# SCH-EC_port.net
KiCad netlist of a schematic drawn in Altium Designer
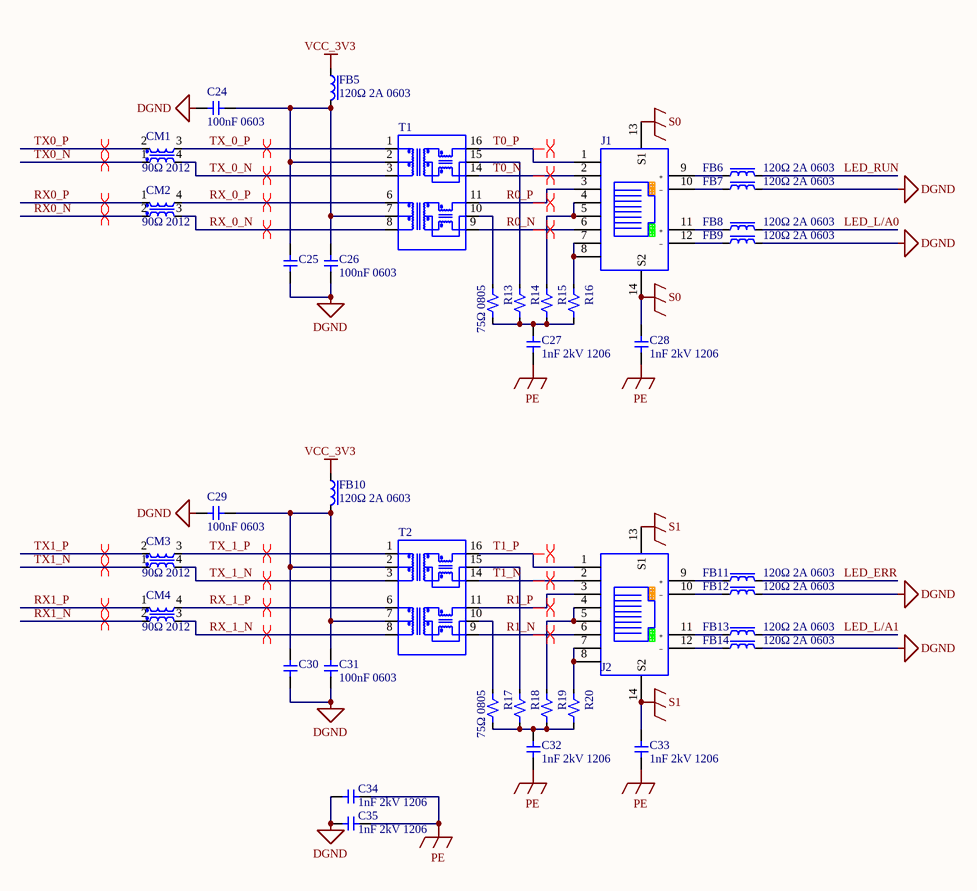
[diagram p0: SCH-EC_port.SchDoc]

(export (version "E")
  (design (tool "Eeschema 10.0.6"))
  (components
    (comp (ref "C24")
      (value "100nF 0603")
      (footprint "CAPC1608X08 (0603)")
      (description "贴片MLCC电容 100nF 50V X7R 10% 0603")
      (fields
        (field (name "1ST PARTNUMBER") "CC0603KRX7R9BB104")
        (field (name "2ND PARTNUMBER") "CGA3E2X7R1H104K080AA")
      )
      (libsource (lib "12-无源器件") (part "100nF 0603"))
    )
    (comp (ref "C25")
      (value "100nF 0603")
      (footprint "CAPC1608X08 (0603)")
      (description "贴片MLCC电容 100nF 50V X7R 10% 0603")
      (fields
        (field (name "1ST PARTNUMBER") "CC0603KRX7R9BB104")
        (field (name "2ND PARTNUMBER") "CGA3E2X7R1H104K080AA")
      )
      (libsource (lib "12-无源器件") (part "100nF 0603"))
    )
    (comp (ref "C26")
      (value "100nF 0603")
      (footprint "CAPC1608X08 (0603)")
      (description "贴片MLCC电容 100nF 50V X7R 10% 0603")
      (fields
        (field (name "1ST PARTNUMBER") "CC0603KRX7R9BB104")
        (field (name "2ND PARTNUMBER") "CGA3E2X7R1H104K080AA")
      )
      (libsource (lib "12-无源器件") (part "100nF 0603"))
    )
    (comp (ref "C27")
      (value "1nF 2kV 1206")
      (footprint "CAPC3216X16 (1206)")
      (description "贴片MLCC电容 1.0nF 2KV X7R 10% 1206")
      (fields (field (name "1ST PARTNUMBER") "CC1206KKX7RDBB102"))
      (libsource (lib "") (part "1nF 2kV 1206_1"))
    )
    (comp (ref "C28")
      (value "1nF 2kV 1206")
      (footprint "CAPC3216X16 (1206)")
      (description "贴片MLCC电容 1.0nF 2KV X7R 10% 1206")
      (fields (field (name "1ST PARTNUMBER") "CC1206KKX7RDBB102"))
      (libsource (lib "12-无源器件") (part "1nF 2kV 1206"))
    )
    (comp (ref "C29")
      (value "100nF 0603")
      (footprint "CAPC1608X08 (0603)")
      (description "贴片MLCC电容 100nF 50V X7R 10% 0603")
      (fields
        (field (name "1ST PARTNUMBER") "CC0603KRX7R9BB104")
        (field (name "2ND PARTNUMBER") "CGA3E2X7R1H104K080AA")
      )
      (libsource (lib "12-无源器件") (part "100nF 0603"))
    )
    (comp (ref "C30")
      (value "100nF 0603")
      (footprint "CAPC1608X08 (0603)")
      (description "贴片MLCC电容 100nF 50V X7R 10% 0603")
      (fields
        (field (name "1ST PARTNUMBER") "CC0603KRX7R9BB104")
        (field (name "2ND PARTNUMBER") "CGA3E2X7R1H104K080AA")
      )
      (libsource (lib "12-无源器件") (part "100nF 0603"))
    )
    (comp (ref "C31")
      (value "100nF 0603")
      (footprint "CAPC1608X08 (0603)")
      (description "贴片MLCC电容 100nF 50V X7R 10% 0603")
      (fields
        (field (name "1ST PARTNUMBER") "CC0603KRX7R9BB104")
        (field (name "2ND PARTNUMBER") "CGA3E2X7R1H104K080AA")
      )
      (libsource (lib "12-无源器件") (part "100nF 0603"))
    )
    (comp (ref "C32")
      (value "1nF 2kV 1206")
      (footprint "CAPC3216X16 (1206)")
      (description "贴片MLCC电容 1.0nF 2KV X7R 10% 1206")
      (fields (field (name "1ST PARTNUMBER") "CC1206KKX7RDBB102"))
      (libsource (lib "") (part "1nF 2kV 1206_1"))
    )
    (comp (ref "C33")
      (value "1nF 2kV 1206")
      (footprint "CAPC3216X16 (1206)")
      (description "贴片MLCC电容 1.0nF 2KV X7R 10% 1206")
      (fields (field (name "1ST PARTNUMBER") "CC1206KKX7RDBB102"))
      (libsource (lib "12-无源器件") (part "1nF 2kV 1206"))
    )
    (comp (ref "C34")
      (value "1nF 2kV 1206")
      (footprint "CAPC3216X16 (1206)")
      (description "贴片MLCC电容 1.0nF 2KV X7R 10% 1206")
      (fields (field (name "1ST PARTNUMBER") "CC1206KKX7RDBB102"))
      (libsource (lib "") (part "1nF 2kV 1206_1"))
    )
    (comp (ref "C35")
      (value "1nF 2kV 1206")
      (footprint "CAPC3216X16 (1206)")
      (description "贴片MLCC电容 1.0nF 2KV X7R 10% 1206")
      (fields (field (name "1ST PARTNUMBER") "CC1206KKX7RDBB102"))
      (libsource (lib "") (part "1nF 2kV 1206_1"))
    )
    (comp (ref "CM1")
      (value "90Ω 2012")
      (footprint "CAF-80P120X200-4N")
      (description "高速信号共模滤波器 90Ω@100MHz, 0.33A, 2012")
      (fields
        (field (name "1ST PARTNUMBER") "SDCW2012-2-900TF")
        (field (name "2ND PARTNUMBER") "ACM2012E-900-2P-T01")
      )
      (libsource (lib "12-无源器件") (part "90Ω@100MHz 2012"))
    )
    (comp (ref "CM2")
      (value "90Ω 2012")
      (footprint "CAF-80P120X200-4N")
      (description "高速信号共模滤波器 90Ω@100MHz, 0.33A, 2012")
      (fields
        (field (name "1ST PARTNUMBER") "SDCW2012-2-900TF")
        (field (name "2ND PARTNUMBER") "ACM2012E-900-2P-T01")
      )
      (libsource (lib "") (part "90Ω@100MHz 2012_1"))
    )
    (comp (ref "CM3")
      (value "90Ω 2012")
      (footprint "CAF-80P120X200-4N")
      (description "高速信号共模滤波器 90Ω@100MHz, 0.33A, 2012")
      (fields
        (field (name "1ST PARTNUMBER") "SDCW2012-2-900TF")
        (field (name "2ND PARTNUMBER") "ACM2012E-900-2P-T01")
      )
      (libsource (lib "12-无源器件") (part "90Ω@100MHz 2012"))
    )
    (comp (ref "CM4")
      (value "90Ω 2012")
      (footprint "CAF-80P120X200-4N")
      (description "高速信号共模滤波器 90Ω@100MHz, 0.33A, 2012")
      (fields
        (field (name "1ST PARTNUMBER") "SDCW2012-2-900TF")
        (field (name "2ND PARTNUMBER") "ACM2012E-900-2P-T01")
      )
      (libsource (lib "") (part "90Ω@100MHz 2012_1"))
    )
    (comp (ref "FB5")
      (value "120Ω 2A 0603")
      (footprint "INDC1608X08 (0603)")
      (description "电源线磁珠 0603 120Ω@100MHz 2A")
      (fields
        (field (name "1ST PARTNUMBER") "PZ1608U121-2R0TF")
        (field (name "2ND PARTNUMBER") "BLM18PG121SN1D")
      )
      (libsource (lib "12-无源器件") (part "120Ω@100MHz 2A 0603"))
    )
    (comp (ref "FB6")
      (value "120Ω 2A 0603")
      (footprint "INDC1608X08 (0603)")
      (description "电源线磁珠 0603 120Ω@100MHz 2A")
      (fields
        (field (name "1ST PARTNUMBER") "PZ1608U121-2R0TF")
        (field (name "2ND PARTNUMBER") "BLM18PG121SN1D")
      )
      (libsource (lib "12-无源器件") (part "120Ω@100MHz 2A 0603"))
    )
    (comp (ref "FB7")
      (value "120Ω 2A 0603")
      (footprint "INDC1608X08 (0603)")
      (description "电源线磁珠 0603 120Ω@100MHz 2A")
      (fields
        (field (name "1ST PARTNUMBER") "PZ1608U121-2R0TF")
        (field (name "2ND PARTNUMBER") "BLM18PG121SN1D")
      )
      (libsource (lib "12-无源器件") (part "120Ω@100MHz 2A 0603"))
    )
    (comp (ref "FB8")
      (value "120Ω 2A 0603")
      (footprint "INDC1608X08 (0603)")
      (description "电源线磁珠 0603 120Ω@100MHz 2A")
      (fields
        (field (name "1ST PARTNUMBER") "PZ1608U121-2R0TF")
        (field (name "2ND PARTNUMBER") "BLM18PG121SN1D")
      )
      (libsource (lib "12-无源器件") (part "120Ω@100MHz 2A 0603"))
    )
    (comp (ref "FB9")
      (value "120Ω 2A 0603")
      (footprint "INDC1608X08 (0603)")
      (description "电源线磁珠 0603 120Ω@100MHz 2A")
      (fields
        (field (name "1ST PARTNUMBER") "PZ1608U121-2R0TF")
        (field (name "2ND PARTNUMBER") "BLM18PG121SN1D")
      )
      (libsource (lib "12-无源器件") (part "120Ω@100MHz 2A 0603"))
    )
    (comp (ref "FB10")
      (value "120Ω 2A 0603")
      (footprint "INDC1608X08 (0603)")
      (description "电源线磁珠 0603 120Ω@100MHz 2A")
      (fields
        (field (name "1ST PARTNUMBER") "PZ1608U121-2R0TF")
        (field (name "2ND PARTNUMBER") "BLM18PG121SN1D")
      )
      (libsource (lib "12-无源器件") (part "120Ω@100MHz 2A 0603"))
    )
    (comp (ref "FB11")
      (value "120Ω 2A 0603")
      (footprint "INDC1608X08 (0603)")
      (description "电源线磁珠 0603 120Ω@100MHz 2A")
      (fields
        (field (name "1ST PARTNUMBER") "PZ1608U121-2R0TF")
        (field (name "2ND PARTNUMBER") "BLM18PG121SN1D")
      )
      (libsource (lib "12-无源器件") (part "120Ω@100MHz 2A 0603"))
    )
    (comp (ref "FB12")
      (value "120Ω 2A 0603")
      (footprint "INDC1608X08 (0603)")
      (description "电源线磁珠 0603 120Ω@100MHz 2A")
      (fields
        (field (name "1ST PARTNUMBER") "PZ1608U121-2R0TF")
        (field (name "2ND PARTNUMBER") "BLM18PG121SN1D")
      )
      (libsource (lib "12-无源器件") (part "120Ω@100MHz 2A 0603"))
    )
    (comp (ref "FB13")
      (value "120Ω 2A 0603")
      (footprint "INDC1608X08 (0603)")
      (description "电源线磁珠 0603 120Ω@100MHz 2A")
      (fields
        (field (name "1ST PARTNUMBER") "PZ1608U121-2R0TF")
        (field (name "2ND PARTNUMBER") "BLM18PG121SN1D")
      )
      (libsource (lib "12-无源器件") (part "120Ω@100MHz 2A 0603"))
    )
    (comp (ref "FB14")
      (value "120Ω 2A 0603")
      (footprint "INDC1608X08 (0603)")
      (description "电源线磁珠 0603 120Ω@100MHz 2A")
      (fields
        (field (name "1ST PARTNUMBER") "PZ1608U121-2R0TF")
        (field (name "2ND PARTNUMBER") "BLM18PG121SN1D")
      )
      (libsource (lib "12-无源器件") (part "120Ω@100MHz 2A 0603"))
    )
    (comp (ref "J1")
      (value "1901-396X")
      (footprint "1901-396X")
      (description "以太网连接器 90度弯 带灯（左黄右绿）金属外壳 EMI弹片")
      (libsource (lib "15-连接器") (part "1901-396X"))
    )
    (comp (ref "J2")
      (value "1901-396X")
      (footprint "1901-396X")
      (description "以太网连接器 90度弯 带灯（左黄右绿）金属外壳 EMI弹片")
      (libsource (lib "15-连接器") (part "1901-396X"))
    )
    (comp (ref "R13")
      (value "75Ω 0805")
      (footprint "RESC2012X05 (0805)")
      (description "贴片厚膜电阻 75Ω 1% 0805")
      (fields
        (field (name "1ST PARTNUMBER") "RC0805FR-0775RL")
        (field (name "2ND PARTNUMBER") "CR0805-FX-75R0ELF")
      )
      (libsource (lib "12-无源器件") (part "75Ω 0805"))
    )
    (comp (ref "R14")
      (value "75Ω 0805")
      (footprint "RESC2012X05 (0805)")
      (description "贴片厚膜电阻 75Ω 1% 0805")
      (fields
        (field (name "1ST PARTNUMBER") "RC0805FR-0775RL")
        (field (name "2ND PARTNUMBER") "CR0805-FX-75R0ELF")
      )
      (libsource (lib "12-无源器件") (part "75Ω 0805"))
    )
    (comp (ref "R15")
      (value "75Ω 0805")
      (footprint "RESC2012X05 (0805)")
      (description "贴片厚膜电阻 75Ω 1% 0805")
      (fields
        (field (name "1ST PARTNUMBER") "RC0805FR-0775RL")
        (field (name "2ND PARTNUMBER") "CR0805-FX-75R0ELF")
      )
      (libsource (lib "12-无源器件") (part "75Ω 0805"))
    )
    (comp (ref "R16")
      (value "75Ω 0805")
      (footprint "RESC2012X05 (0805)")
      (description "贴片厚膜电阻 75Ω 1% 0805")
      (fields
        (field (name "1ST PARTNUMBER") "RC0805FR-0775RL")
        (field (name "2ND PARTNUMBER") "CR0805-FX-75R0ELF")
      )
      (libsource (lib "12-无源器件") (part "75Ω 0805"))
    )
    (comp (ref "R17")
      (value "75Ω 0805")
      (footprint "RESC2012X05 (0805)")
      (description "贴片厚膜电阻 75Ω 1% 0805")
      (fields
        (field (name "1ST PARTNUMBER") "RC0805FR-0775RL")
        (field (name "2ND PARTNUMBER") "CR0805-FX-75R0ELF")
      )
      (libsource (lib "12-无源器件") (part "75Ω 0805"))
    )
    (comp (ref "R18")
      (value "75Ω 0805")
      (footprint "RESC2012X05 (0805)")
      (description "贴片厚膜电阻 75Ω 1% 0805")
      (fields
        (field (name "1ST PARTNUMBER") "RC0805FR-0775RL")
        (field (name "2ND PARTNUMBER") "CR0805-FX-75R0ELF")
      )
      (libsource (lib "12-无源器件") (part "75Ω 0805"))
    )
    (comp (ref "R19")
      (value "75Ω 0805")
      (footprint "RESC2012X05 (0805)")
      (description "贴片厚膜电阻 75Ω 1% 0805")
      (fields
        (field (name "1ST PARTNUMBER") "RC0805FR-0775RL")
        (field (name "2ND PARTNUMBER") "CR0805-FX-75R0ELF")
      )
      (libsource (lib "12-无源器件") (part "75Ω 0805"))
    )
    (comp (ref "R20")
      (value "75Ω 0805")
      (footprint "RESC2012X05 (0805)")
      (description "贴片厚膜电阻 75Ω 1% 0805")
      (fields
        (field (name "1ST PARTNUMBER") "RC0805FR-0775RL")
        (field (name "2ND PARTNUMBER") "CR0805-FX-75R0ELF")
      )
      (libsource (lib "12-无源器件") (part "75Ω 0805"))
    )
    (comp (ref "T1")
      (value "H1601CE")
      (footprint "SOIC127P940X640-16N")
      (description "单口百兆网络隔离变压器")
      (fields (field (name "2ND PARTNUMBER") "H1102NL"))
      (libsource (lib "12-无源器件") (part "H1601CE"))
    )
    (comp (ref "T2")
      (value "H1601CE")
      (footprint "SOIC127P940X640-16N")
      (description "单口百兆网络隔离变压器")
      (fields (field (name "2ND PARTNUMBER") "H1102NL"))
      (libsource (lib "12-无源器件") (part "H1601CE"))
    )
  )
  (nets
    (net (code "1") (name "/LED_ERR") (class "Default")
      (node (ref "FB11") (pin "2") (pinfunction "2_2") (pintype "passive"))
    )
    (net (code "2") (name "/LED_L{slash}A0") (class "Default")
      (node (ref "FB8") (pin "2") (pinfunction "2_2") (pintype "passive"))
    )
    (net (code "3") (name "/LED_L{slash}A1") (class "Default")
      (node (ref "FB13") (pin "2") (pinfunction "2_2") (pintype "passive"))
    )
    (net (code "4") (name "/LED_RUN") (class "Default")
      (node (ref "FB6") (pin "2") (pinfunction "2_2") (pintype "passive"))
    )
    (net (code "5") (name "/R0_N") (class "Default")
      (node (ref "J1") (pin "6") (pinfunction "Rx-_6") (pintype "passive"))
      (node (ref "T1") (pin "9") (pinfunction "9_9") (pintype "passive"))
    )
    (net (code "6") (name "/R0_P") (class "Default")
      (node (ref "J1") (pin "3") (pinfunction "Rx+_3") (pintype "passive"))
      (node (ref "T1") (pin "11") (pinfunction "11_11") (pintype "passive"))
    )
    (net (code "7") (name "/R1_N") (class "Default")
      (node (ref "J2") (pin "6") (pinfunction "Rx-_6") (pintype "passive"))
      (node (ref "T2") (pin "9") (pinfunction "9_9") (pintype "passive"))
    )
    (net (code "8") (name "/R1_P") (class "Default")
      (node (ref "J2") (pin "3") (pinfunction "Rx+_3") (pintype "passive"))
      (node (ref "T2") (pin "11") (pinfunction "11_11") (pintype "passive"))
    )
    (net (code "9") (name "/RX0_N") (class "Default")
      (node (ref "CM2") (pin "2") (pinfunction "2_2") (pintype "passive"))
    )
    (net (code "10") (name "/RX0_P") (class "Default")
      (node (ref "CM2") (pin "1") (pinfunction "1_1") (pintype "passive"))
    )
    (net (code "11") (name "/RX1_N") (class "Default")
      (node (ref "CM4") (pin "2") (pinfunction "2_2") (pintype "passive"))
    )
    (net (code "12") (name "/RX1_P") (class "Default")
      (node (ref "CM4") (pin "1") (pinfunction "1_1") (pintype "passive"))
    )
    (net (code "13") (name "/RX_0_N") (class "Default")
      (node (ref "CM2") (pin "3") (pinfunction "3_3") (pintype "passive"))
      (node (ref "T1") (pin "8") (pinfunction "8_8") (pintype "passive"))
    )
    (net (code "14") (name "/RX_0_P") (class "Default")
      (node (ref "CM2") (pin "4") (pinfunction "4_4") (pintype "passive"))
      (node (ref "T1") (pin "6") (pinfunction "6_6") (pintype "passive"))
    )
    (net (code "15") (name "/RX_1_N") (class "Default")
      (node (ref "CM4") (pin "3") (pinfunction "3_3") (pintype "passive"))
      (node (ref "T2") (pin "8") (pinfunction "8_8") (pintype "passive"))
    )
    (net (code "16") (name "/RX_1_P") (class "Default")
      (node (ref "CM4") (pin "4") (pinfunction "4_4") (pintype "passive"))
      (node (ref "T2") (pin "6") (pinfunction "6_6") (pintype "passive"))
    )
    (net (code "17") (name "/T0_N") (class "Default")
      (node (ref "J1") (pin "2") (pinfunction "Tx-_2") (pintype "passive"))
      (node (ref "T1") (pin "14") (pinfunction "14_14") (pintype "passive"))
    )
    (net (code "18") (name "/T0_P") (class "Default")
      (node (ref "J1") (pin "1") (pinfunction "Tx+_1") (pintype "passive"))
      (node (ref "T1") (pin "16") (pinfunction "16_16") (pintype "passive"))
    )
    (net (code "19") (name "/T1_N") (class "Default")
      (node (ref "J2") (pin "2") (pinfunction "Tx-_2") (pintype "passive"))
      (node (ref "T2") (pin "14") (pinfunction "14_14") (pintype "passive"))
    )
    (net (code "20") (name "/T1_P") (class "Default")
      (node (ref "J2") (pin "1") (pinfunction "Tx+_1") (pintype "passive"))
      (node (ref "T2") (pin "16") (pinfunction "16_16") (pintype "passive"))
    )
    (net (code "21") (name "/TX0_N") (class "Default")
      (node (ref "CM1") (pin "1") (pinfunction "1_1") (pintype "passive"))
    )
    (net (code "22") (name "/TX0_P") (class "Default")
      (node (ref "CM1") (pin "2") (pinfunction "2_2") (pintype "passive"))
    )
    (net (code "23") (name "/TX1_N") (class "Default")
      (node (ref "CM3") (pin "1") (pinfunction "1_1") (pintype "passive"))
    )
    (net (code "24") (name "/TX1_P") (class "Default")
      (node (ref "CM3") (pin "2") (pinfunction "2_2") (pintype "passive"))
    )
    (net (code "25") (name "/TX_0_N") (class "Default")
      (node (ref "CM1") (pin "4") (pinfunction "4_4") (pintype "passive"))
      (node (ref "T1") (pin "3") (pinfunction "3_3") (pintype "passive"))
    )
    (net (code "26") (name "/TX_0_P") (class "Default")
      (node (ref "CM1") (pin "3") (pinfunction "3_3") (pintype "passive"))
      (node (ref "T1") (pin "1") (pinfunction "1_1") (pintype "passive"))
    )
    (net (code "27") (name "/TX_1_N") (class "Default")
      (node (ref "CM3") (pin "4") (pinfunction "4_4") (pintype "passive"))
      (node (ref "T2") (pin "3") (pinfunction "3_3") (pintype "passive"))
    )
    (net (code "28") (name "/TX_1_P") (class "Default")
      (node (ref "CM3") (pin "3") (pinfunction "3_3") (pintype "passive"))
      (node (ref "T2") (pin "1") (pinfunction "1_1") (pintype "passive"))
    )
    (net (code "29") (name "DGND") (class "Default")
      (node (ref "C24") (pin "2") (pinfunction "2_2") (pintype "passive"))
      (node (ref "C25") (pin "2") (pinfunction "2_2") (pintype "passive"))
      (node (ref "C26") (pin "2") (pinfunction "2_2") (pintype "passive"))
      (node (ref "C29") (pin "2") (pinfunction "2_2") (pintype "passive"))
      (node (ref "C30") (pin "2") (pinfunction "2_2") (pintype "passive"))
      (node (ref "C31") (pin "2") (pinfunction "2_2") (pintype "passive"))
      (node (ref "C34") (pin "1") (pinfunction "1_1") (pintype "passive"))
      (node (ref "C35") (pin "1") (pinfunction "1_1") (pintype "passive"))
      (node (ref "FB12") (pin "2") (pinfunction "2_2") (pintype "passive"))
      (node (ref "FB14") (pin "2") (pinfunction "2_2") (pintype "passive"))
      (node (ref "FB7") (pin "2") (pinfunction "2_2") (pintype "passive"))
      (node (ref "FB9") (pin "2") (pinfunction "2_2") (pintype "passive"))
    )
    (net (code "30") (name "Net-(C24-Pad1)") (class "Default")
      (node (ref "C24") (pin "1") (pinfunction "1_1") (pintype "passive"))
      (node (ref "C25") (pin "1") (pinfunction "1_1") (pintype "passive"))
      (node (ref "C26") (pin "1") (pinfunction "1_1") (pintype "passive"))
      (node (ref "FB5") (pin "2") (pinfunction "2_2") (pintype "passive"))
      (node (ref "T1") (pin "2") (pinfunction "2_2") (pintype "passive"))
      (node (ref "T1") (pin "7") (pinfunction "7_7") (pintype "passive"))
    )
    (net (code "31") (name "Net-(C27-Pad1)") (class "Default")
      (node (ref "C27") (pin "1") (pinfunction "1_1") (pintype "passive"))
      (node (ref "R13") (pin "1") (pinfunction "1_1") (pintype "passive"))
      (node (ref "R14") (pin "1") (pinfunction "1_1") (pintype "passive"))
      (node (ref "R15") (pin "1") (pinfunction "1_1") (pintype "passive"))
      (node (ref "R16") (pin "1") (pinfunction "1_1") (pintype "passive"))
    )
    (net (code "32") (name "Net-(C29-Pad1)") (class "Default")
      (node (ref "C29") (pin "1") (pinfunction "1_1") (pintype "passive"))
      (node (ref "C30") (pin "1") (pinfunction "1_1") (pintype "passive"))
      (node (ref "C31") (pin "1") (pinfunction "1_1") (pintype "passive"))
      (node (ref "FB10") (pin "2") (pinfunction "2_2") (pintype "passive"))
      (node (ref "T2") (pin "2") (pinfunction "2_2") (pintype "passive"))
      (node (ref "T2") (pin "7") (pinfunction "7_7") (pintype "passive"))
    )
    (net (code "33") (name "Net-(C32-Pad1)") (class "Default")
      (node (ref "C32") (pin "1") (pinfunction "1_1") (pintype "passive"))
      (node (ref "R17") (pin "1") (pinfunction "1_1") (pintype "passive"))
      (node (ref "R18") (pin "1") (pinfunction "1_1") (pintype "passive"))
      (node (ref "R19") (pin "1") (pinfunction "1_1") (pintype "passive"))
      (node (ref "R20") (pin "1") (pinfunction "1_1") (pintype "passive"))
    )
    (net (code "34") (name "Net-(FB6-Pad1)") (class "Default")
      (node (ref "FB6") (pin "1") (pinfunction "1_1") (pintype "passive"))
      (node (ref "J1") (pin "9") (pinfunction "﹢_9") (pintype "passive"))
    )
    (net (code "35") (name "Net-(FB7-Pad1)") (class "Default")
      (node (ref "FB7") (pin "1") (pinfunction "1_1") (pintype "passive"))
      (node (ref "J1") (pin "10") (pinfunction "﹣_10") (pintype "passive"))
    )
    (net (code "36") (name "Net-(FB8-Pad1)") (class "Default")
      (node (ref "FB8") (pin "1") (pinfunction "1_1") (pintype "passive"))
      (node (ref "J1") (pin "11") (pinfunction "﹢_11") (pintype "passive"))
    )
    (net (code "37") (name "Net-(FB9-Pad1)") (class "Default")
      (node (ref "FB9") (pin "1") (pinfunction "1_1") (pintype "passive"))
      (node (ref "J1") (pin "12") (pinfunction "﹣_12") (pintype "passive"))
    )
    (net (code "38") (name "Net-(FB11-Pad1)") (class "Default")
      (node (ref "FB11") (pin "1") (pinfunction "1_1") (pintype "passive"))
      (node (ref "J2") (pin "9") (pinfunction "﹢_9") (pintype "passive"))
    )
    (net (code "39") (name "Net-(FB12-Pad1)") (class "Default")
      (node (ref "FB12") (pin "1") (pinfunction "1_1") (pintype "passive"))
      (node (ref "J2") (pin "10") (pinfunction "﹣_10") (pintype "passive"))
    )
    (net (code "40") (name "Net-(FB13-Pad1)") (class "Default")
      (node (ref "FB13") (pin "1") (pinfunction "1_1") (pintype "passive"))
      (node (ref "J2") (pin "11") (pinfunction "﹢_11") (pintype "passive"))
    )
    (net (code "41") (name "Net-(FB14-Pad1)") (class "Default")
      (node (ref "FB14") (pin "1") (pinfunction "1_1") (pintype "passive"))
      (node (ref "J2") (pin "12") (pinfunction "﹣_12") (pintype "passive"))
    )
    (net (code "42") (name "Net-(J1-Pad4)") (class "Default")
      (node (ref "J1") (pin "4") (pinfunction "4_4") (pintype "passive"))
      (node (ref "J1") (pin "5") (pinfunction "5_5") (pintype "passive"))
      (node (ref "R15") (pin "2") (pinfunction "2_2") (pintype "passive"))
    )
    (net (code "43") (name "Net-(J1-Pad7)") (class "Default")
      (node (ref "J1") (pin "7") (pinfunction "7_7") (pintype "passive"))
      (node (ref "J1") (pin "8") (pinfunction "8_8") (pintype "passive"))
      (node (ref "R16") (pin "2") (pinfunction "2_2") (pintype "passive"))
    )
    (net (code "44") (name "Net-(J2-Pad4)") (class "Default")
      (node (ref "J2") (pin "4") (pinfunction "4_4") (pintype "passive"))
      (node (ref "J2") (pin "5") (pinfunction "5_5") (pintype "passive"))
      (node (ref "R19") (pin "2") (pinfunction "2_2") (pintype "passive"))
    )
    (net (code "45") (name "Net-(J2-Pad7)") (class "Default")
      (node (ref "J2") (pin "7") (pinfunction "7_7") (pintype "passive"))
      (node (ref "J2") (pin "8") (pinfunction "8_8") (pintype "passive"))
      (node (ref "R20") (pin "2") (pinfunction "2_2") (pintype "passive"))
    )
    (net (code "46") (name "Net-(R13-Pad2)") (class "Default")
      (node (ref "R13") (pin "2") (pinfunction "2_2") (pintype "passive"))
      (node (ref "T1") (pin "10") (pinfunction "10_10") (pintype "passive"))
    )
    (net (code "47") (name "Net-(R14-Pad2)") (class "Default")
      (node (ref "R14") (pin "2") (pinfunction "2_2") (pintype "passive"))
      (node (ref "T1") (pin "15") (pinfunction "15_15") (pintype "passive"))
    )
    (net (code "48") (name "Net-(R17-Pad2)") (class "Default")
      (node (ref "R17") (pin "2") (pinfunction "2_2") (pintype "passive"))
      (node (ref "T2") (pin "10") (pinfunction "10_10") (pintype "passive"))
    )
    (net (code "49") (name "Net-(R18-Pad2)") (class "Default")
      (node (ref "R18") (pin "2") (pinfunction "2_2") (pintype "passive"))
      (node (ref "T2") (pin "15") (pinfunction "15_15") (pintype "passive"))
    )
    (net (code "50") (name "PE") (class "Default")
      (node (ref "C27") (pin "2") (pinfunction "2_2") (pintype "passive"))
      (node (ref "C28") (pin "2") (pinfunction "2_2") (pintype "passive"))
      (node (ref "C32") (pin "2") (pinfunction "2_2") (pintype "passive"))
      (node (ref "C33") (pin "2") (pinfunction "2_2") (pintype "passive"))
      (node (ref "C34") (pin "2") (pinfunction "2_2") (pintype "passive"))
      (node (ref "C35") (pin "2") (pinfunction "2_2") (pintype "passive"))
    )
    (net (code "51") (name "S0") (class "Default")
      (node (ref "C28") (pin "1") (pinfunction "1_1") (pintype "passive"))
      (node (ref "J1") (pin "13") (pinfunction "S1_13") (pintype "passive"))
      (node (ref "J1") (pin "14") (pinfunction "S2_14") (pintype "passive"))
    )
    (net (code "52") (name "S1") (class "Default")
      (node (ref "C33") (pin "1") (pinfunction "1_1") (pintype "passive"))
      (node (ref "J2") (pin "13") (pinfunction "S1_13") (pintype "passive"))
      (node (ref "J2") (pin "14") (pinfunction "S2_14") (pintype "passive"))
    )
    (net (code "53") (name "VCC_3V3") (class "Default")
      (node (ref "FB10") (pin "1") (pinfunction "1_1") (pintype "passive"))
      (node (ref "FB5") (pin "1") (pinfunction "1_1") (pintype "passive"))
    )
  )
)
